# MSP430.net
KiCad netlist of a schematic drawn in Altium Designer
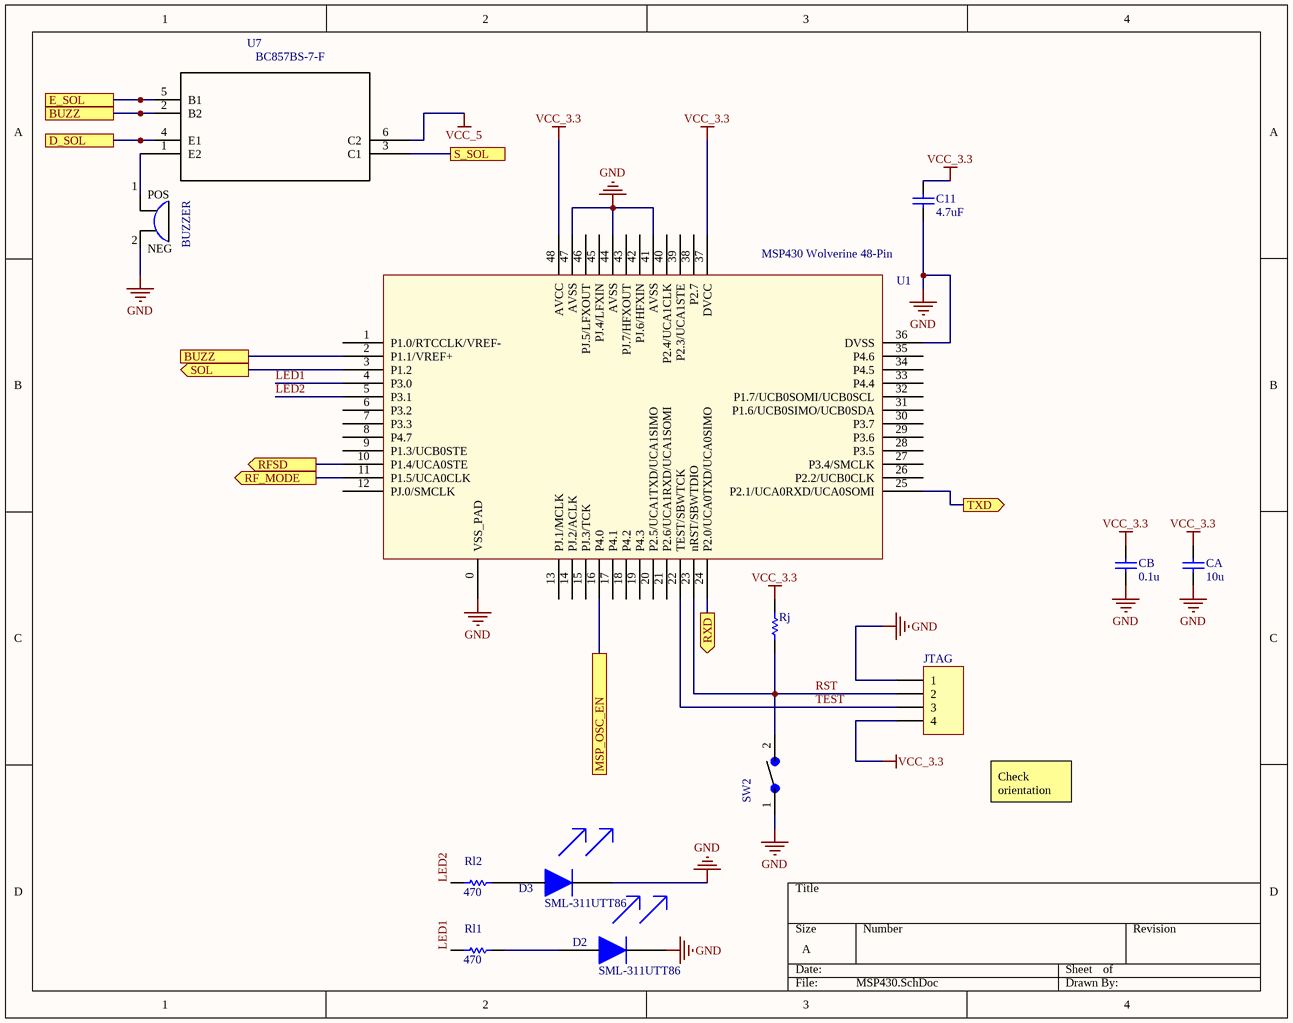
[diagram p0: MSP430.SchDoc]

(export (version "E")
  (design (tool "Eeschema 10.0.6"))
  (components
    (comp (ref "BUZZER")
      (value "MCKPM-G1201A-K4037")
      (footprint "XDCR_MCKPM-G1201A-K4037")
      (description "Magnetic Buzzer And Transducer")
      (fields (field (name "MF") "Multicomp"))
      (libsource (lib "MCKPM-G1201A-K4037") (part "MCKPM-G1201A-K4037"))
    )
    (comp (ref "C11")
      (value "4.7uF")
      (footprint "0402-W")
      (description "Ceramic Capacitor (Surface Mount)")
      (fields (field (name "MANUFACTURER") "Generic Ceramic Chip Cap (TBD)") (field (name "Comment") "Cap"))
      (libsource (lib "WISP_AD10") (part "Cap"))
    )
    (comp (ref "CA")
      (value "10u")
      (footprint "0402-W")
      (description "Ceramic Capacitor (Surface Mount)")
      (fields (field (name "MANUFACTURER") "Generic Ceramic Chip Cap (TBD)") (field (name "Comment") "Cap"))
      (libsource (lib "wisp") (part "Cap"))
    )
    (comp (ref "CB")
      (value "0.1u")
      (footprint "0402-W")
      (description "Ceramic Capacitor (Surface Mount)")
      (fields (field (name "MANUFACTURER") "Generic Ceramic Chip Cap (TBD)") (field (name "Comment") "Cap"))
      (libsource (lib "wisp") (part "Cap"))
    )
    (comp (ref "D2")
      (value "SML-311UTT86")
      (footprint "0603")
      (description "LED 630NM RED WTR CLR 0603 SMD")
      (libsource (lib "Fromm") (part "SML-311UTT86"))
    )
    (comp (ref "D3")
      (value "SML-311UTT86")
      (footprint "0603")
      (description "LED 630NM RED WTR CLR 0603 SMD")
      (libsource (lib "Fromm") (part "SML-311UTT86"))
    )
    (comp (ref "JTAG")
      (value "MHDR1X4")
      (footprint "MHDR1X4")
      (description "Header, 4-Pin")
      (fields (field (name "PUBLISHER") "Altium Limited"))
      (libsource (lib "Miscellaneous Connectors") (part "MHDR1X4"))
    )
    (comp (ref "Rj")
      (value "Res")
      (footprint "0402")
      (description "Chip Resistor (Surface Mount)")
      (fields (field (name "MANUFACTURER") "Generic Chip Res (TBD)"))
      (libsource (lib "WISP_AD10") (part "Res"))
    )
    (comp (ref "Rl1")
      (value "470")
      (footprint "0402")
      (description "Chip Resistor (Surface Mount)")
      (fields (field (name "MANUFACTURER") "Generic Chip Res (TBD)") (field (name "Comment") "Res"))
      (libsource (lib "wisp") (part "Res"))
    )
    (comp (ref "Rl2")
      (value "470")
      (footprint "0402")
      (description "Chip Resistor (Surface Mount)")
      (fields (field (name "MANUFACTURER") "Generic Chip Res (TBD)") (field (name "Comment") "Res"))
      (libsource (lib "wisp") (part "Res"))
    )
    (comp (ref "SW2")
      (value "FSMSM _1437566-3_")
      (footprint "TE_FSMSM")
      (description "FSMSM=3.5X6 SMT TACT")
      (fields (field (name "MF") "TE Connectivity") (field (name "MP") "FSMSM"))
      (libsource (lib "FSMSM") (part "FSMSM"))
    )
    (comp (ref "U1")
      (value "MSP430 Wolverine 48-Pin")
      (footprint "MSP_QFN48_RGZ_PAD0")
      (description "16-bit FRAM MCU")
      (libsource (lib "wisp") (part "MSP430FR596X_586X_RGZ"))
    )
    (comp (ref "U7")
      (value "BC857BS-7-F")
      (footprint "SOT65P210X100-6N")
      (description "BC857BS Series PNP 45 V 200 mW Small Signal Transistor SMT - SOT-363")
      (fields (field (name "MF") "Diodes Inc."))
      (libsource (lib "BC857BS-7-F") (part "BC857BS-7-F"))
    )
  )
  (nets
    (net (code "1") (name "/BUZZ") (class "Default")
      (node (ref "U1") (pin "2") (pinfunction "P1.1/VREF+_2") (pintype "passive"))
      (node (ref "U7") (pin "2") (pinfunction "B2_2") (pintype "passive"))
    )
    (net (code "2") (name "/D_SOL") (class "Default")
      (node (ref "U7") (pin "4") (pinfunction "E1_4") (pintype "passive"))
    )
    (net (code "3") (name "/E_SOL") (class "Default")
      (node (ref "U7") (pin "5") (pinfunction "B1_5") (pintype "passive"))
    )
    (net (code "4") (name "/LED1") (class "Default")
      (node (ref "Rl1") (pin "2") (pinfunction "2_2") (pintype "passive"))
      (node (ref "U1") (pin "4") (pinfunction "P3.0_4") (pintype "passive"))
    )
    (net (code "5") (name "/LED2") (class "Default")
      (node (ref "Rl2") (pin "2") (pinfunction "2_2") (pintype "passive"))
      (node (ref "U1") (pin "5") (pinfunction "P3.1_5") (pintype "passive"))
    )
    (net (code "6") (name "/MSP_OSC_EN") (class "Default")
      (node (ref "U1") (pin "16") (pinfunction "P4.0_16") (pintype "passive"))
    )
    (net (code "7") (name "/RFSD") (class "Default")
      (node (ref "U1") (pin "10") (pinfunction "P1.4/UCA0STE_10") (pintype "passive"))
    )
    (net (code "8") (name "/RF_MODE") (class "Default")
      (node (ref "U1") (pin "11") (pinfunction "P1.5/UCA0CLK_11") (pintype "passive"))
    )
    (net (code "9") (name "/RST") (class "Default")
      (node (ref "JTAG") (pin "2") (pinfunction "2_2") (pintype "passive"))
      (node (ref "Rj") (pin "1") (pinfunction "1_1") (pintype "passive"))
      (node (ref "SW2") (pin "2") (pinfunction "2_2") (pintype "passive"))
      (node (ref "U1") (pin "23") (pinfunction "nRST/SBWTDIO_23") (pintype "passive"))
    )
    (net (code "10") (name "/RXD") (class "Default")
      (node (ref "U1") (pin "24") (pinfunction "P2.0/UCA0TXD/UCA0SIMO_24") (pintype "passive"))
    )
    (net (code "11") (name "/SOL") (class "Default")
      (node (ref "U1") (pin "3") (pinfunction "P1.2_3") (pintype "passive"))
    )
    (net (code "12") (name "/S_SOL") (class "Default")
      (node (ref "U7") (pin "3") (pinfunction "C1_3") (pintype "passive"))
    )
    (net (code "13") (name "/TEST") (class "Default")
      (node (ref "JTAG") (pin "3") (pinfunction "3_3") (pintype "passive"))
      (node (ref "U1") (pin "22") (pinfunction "TEST/SBWTCK_22") (pintype "passive"))
    )
    (net (code "14") (name "/TXD") (class "Default")
      (node (ref "U1") (pin "25") (pinfunction "P2.1/UCA0RXD/UCA0SOMI_25") (pintype "passive"))
    )
    (net (code "15") (name "GND") (class "Default")
      (node (ref "BUZZER") (pin "2") (pinfunction "NEG_2") (pintype "passive"))
      (node (ref "C11") (pin "1") (pinfunction "1_1") (pintype "passive"))
      (node (ref "CA") (pin "1") (pinfunction "1_1") (pintype "passive"))
      (node (ref "CB") (pin "1") (pinfunction "1_1") (pintype "passive"))
      (node (ref "D2") (pin "2") (pintype "passive"))
      (node (ref "D3") (pin "2") (pintype "passive"))
      (node (ref "JTAG") (pin "1") (pinfunction "1_1") (pintype "passive"))
      (node (ref "SW2") (pin "1") (pinfunction "1_1") (pintype "passive"))
      (node (ref "U1") (pin "0") (pinfunction "VSS_PAD_0") (pintype "passive"))
      (node (ref "U1") (pin "36") (pinfunction "DVSS_36") (pintype "passive"))
      (node (ref "U1") (pin "41") (pinfunction "AVSS_41") (pintype "passive"))
      (node (ref "U1") (pin "44") (pinfunction "AVSS_44") (pintype "passive"))
      (node (ref "U1") (pin "47") (pinfunction "AVSS_47") (pintype "passive"))
    )
    (net (code "16") (name "Net-(BUZZER-POS)") (class "Default")
      (node (ref "BUZZER") (pin "1") (pinfunction "POS_1") (pintype "passive"))
      (node (ref "U7") (pin "1") (pinfunction "E2_1") (pintype "passive"))
    )
    (net (code "17") (name "Net-(D2-Pad1)") (class "Default")
      (node (ref "D2") (pin "1") (pintype "passive"))
      (node (ref "Rl1") (pin "1") (pinfunction "1_1") (pintype "passive"))
    )
    (net (code "18") (name "Net-(D3-Pad1)") (class "Default")
      (node (ref "D3") (pin "1") (pintype "passive"))
      (node (ref "Rl2") (pin "1") (pinfunction "1_1") (pintype "passive"))
    )
    (net (code "19") (name "VCC_3.3") (class "Default")
      (node (ref "C11") (pin "2") (pinfunction "2_2") (pintype "passive"))
      (node (ref "CA") (pin "2") (pinfunction "2_2") (pintype "passive"))
      (node (ref "CB") (pin "2") (pinfunction "2_2") (pintype "passive"))
      (node (ref "JTAG") (pin "4") (pinfunction "4_4") (pintype "passive"))
      (node (ref "Rj") (pin "2") (pinfunction "2_2") (pintype "passive"))
      (node (ref "U1") (pin "37") (pinfunction "DVCC_37") (pintype "passive"))
      (node (ref "U1") (pin "48") (pinfunction "AVCC_48") (pintype "passive"))
    )
    (net (code "20") (name "VCC_5") (class "Default")
      (node (ref "U7") (pin "6") (pinfunction "C2_6") (pintype "passive"))
    )
    (net (code "21") (name "unconnected-(U1-P1.0{slash}RTCCLK{slash}VREF--Pad1)") (class "Default")
      (node (ref "U1") (pin "1") (pinfunction "P1.0/RTCCLK/VREF-_1") (pintype "passive"))
    )
    (net (code "22") (name "unconnected-(U1-P1.3{slash}UCB0STE-Pad9)") (class "Default")
      (node (ref "U1") (pin "9") (pinfunction "P1.3/UCB0STE_9") (pintype "passive"))
    )
    (net (code "23") (name "unconnected-(U1-P1.6{slash}UCB0SIMO{slash}UCB0SDA-Pad31)") (class "Default")
      (node (ref "U1") (pin "31") (pinfunction "P1.6/UCB0SIMO/UCB0SDA_31") (pintype "passive"))
    )
    (net (code "24") (name "unconnected-(U1-P1.7{slash}UCB0SOMI{slash}UCB0SCL-Pad32)") (class "Default")
      (node (ref "U1") (pin "32") (pinfunction "P1.7/UCB0SOMI/UCB0SCL_32") (pintype "passive"))
    )
    (net (code "25") (name "unconnected-(U1-P2.2{slash}UCB0CLK-Pad26)") (class "Default")
      (node (ref "U1") (pin "26") (pinfunction "P2.2/UCB0CLK_26") (pintype "passive"))
    )
    (net (code "26") (name "unconnected-(U1-P2.3{slash}UCA1STE-Pad39)") (class "Default")
      (node (ref "U1") (pin "39") (pinfunction "P2.3/UCA1STE_39") (pintype "passive"))
    )
    (net (code "27") (name "unconnected-(U1-P2.4{slash}UCA1CLK-Pad40)") (class "Default")
      (node (ref "U1") (pin "40") (pinfunction "P2.4/UCA1CLK_40") (pintype "passive"))
    )
    (net (code "28") (name "unconnected-(U1-P2.5{slash}UCA1TXD{slash}UCA1SIMO-Pad20)") (class "Default")
      (node (ref "U1") (pin "20") (pinfunction "P2.5/UCA1TXD/UCA1SIMO_20") (pintype "passive"))
    )
    (net (code "29") (name "unconnected-(U1-P2.6{slash}UCA1RXD{slash}UCA1SOMI-Pad21)") (class "Default")
      (node (ref "U1") (pin "21") (pinfunction "P2.6/UCA1RXD/UCA1SOMI_21") (pintype "passive"))
    )
    (net (code "30") (name "unconnected-(U1-P2.7-Pad38)") (class "Default")
      (node (ref "U1") (pin "38") (pinfunction "P2.7_38") (pintype "passive"))
    )
    (net (code "31") (name "unconnected-(U1-P3.2-Pad6)") (class "Default")
      (node (ref "U1") (pin "6") (pinfunction "P3.2_6") (pintype "passive"))
    )
    (net (code "32") (name "unconnected-(U1-P3.3-Pad7)") (class "Default")
      (node (ref "U1") (pin "7") (pinfunction "P3.3_7") (pintype "passive"))
    )
    (net (code "33") (name "unconnected-(U1-P3.4{slash}SMCLK-Pad27)") (class "Default")
      (node (ref "U1") (pin "27") (pinfunction "P3.4/SMCLK_27") (pintype "passive"))
    )
    (net (code "34") (name "unconnected-(U1-P3.5-Pad28)") (class "Default")
      (node (ref "U1") (pin "28") (pinfunction "P3.5_28") (pintype "passive"))
    )
    (net (code "35") (name "unconnected-(U1-P3.6-Pad29)") (class "Default")
      (node (ref "U1") (pin "29") (pinfunction "P3.6_29") (pintype "passive"))
    )
    (net (code "36") (name "unconnected-(U1-P3.7-Pad30)") (class "Default")
      (node (ref "U1") (pin "30") (pinfunction "P3.7_30") (pintype "passive"))
    )
    (net (code "37") (name "unconnected-(U1-P4.1-Pad17)") (class "Default")
      (node (ref "U1") (pin "17") (pinfunction "P4.1_17") (pintype "passive"))
    )
    (net (code "38") (name "unconnected-(U1-P4.2-Pad18)") (class "Default")
      (node (ref "U1") (pin "18") (pinfunction "P4.2_18") (pintype "passive"))
    )
    (net (code "39") (name "unconnected-(U1-P4.3-Pad19)") (class "Default")
      (node (ref "U1") (pin "19") (pinfunction "P4.3_19") (pintype "passive"))
    )
    (net (code "40") (name "unconnected-(U1-P4.4-Pad33)") (class "Default")
      (node (ref "U1") (pin "33") (pinfunction "P4.4_33") (pintype "passive"))
    )
    (net (code "41") (name "unconnected-(U1-P4.5-Pad34)") (class "Default")
      (node (ref "U1") (pin "34") (pinfunction "P4.5_34") (pintype "passive"))
    )
    (net (code "42") (name "unconnected-(U1-P4.6-Pad35)") (class "Default")
      (node (ref "U1") (pin "35") (pinfunction "P4.6_35") (pintype "passive"))
    )
    (net (code "43") (name "unconnected-(U1-P4.7-Pad8)") (class "Default")
      (node (ref "U1") (pin "8") (pinfunction "P4.7_8") (pintype "passive"))
    )
    (net (code "44") (name "unconnected-(U1-PJ.0{slash}SMCLK-Pad12)") (class "Default")
      (node (ref "U1") (pin "12") (pinfunction "PJ.0/SMCLK_12") (pintype "passive"))
    )
    (net (code "45") (name "unconnected-(U1-PJ.1{slash}MCLK-Pad13)") (class "Default")
      (node (ref "U1") (pin "13") (pinfunction "PJ.1/MCLK_13") (pintype "passive"))
    )
    (net (code "46") (name "unconnected-(U1-PJ.2{slash}ACLK-Pad14)") (class "Default")
      (node (ref "U1") (pin "14") (pinfunction "PJ.2/ACLK_14") (pintype "passive"))
    )
    (net (code "47") (name "unconnected-(U1-PJ.3{slash}TCK-Pad15)") (class "Default")
      (node (ref "U1") (pin "15") (pinfunction "PJ.3/TCK_15") (pintype "passive"))
    )
    (net (code "48") (name "unconnected-(U1-PJ.4{slash}LFXIN-Pad45)") (class "Default")
      (node (ref "U1") (pin "45") (pinfunction "PJ.4/LFXIN_45") (pintype "passive"))
    )
    (net (code "49") (name "unconnected-(U1-PJ.5{slash}LFXOUT-Pad46)") (class "Default")
      (node (ref "U1") (pin "46") (pinfunction "PJ.5/LFXOUT_46") (pintype "passive"))
    )
    (net (code "50") (name "unconnected-(U1-PJ.6{slash}HFXIN-Pad42)") (class "Default")
      (node (ref "U1") (pin "42") (pinfunction "PJ.6/HFXIN_42") (pintype "passive"))
    )
    (net (code "51") (name "unconnected-(U1-PJ.7{slash}HFXOUT-Pad43)") (class "Default")
      (node (ref "U1") (pin "43") (pinfunction "PJ.7/HFXOUT_43") (pintype "passive"))
    )
  )
)
